# Temperature_sensing_and_heater_power.net
KiCad netlist of a schematic drawn in Altium Designer
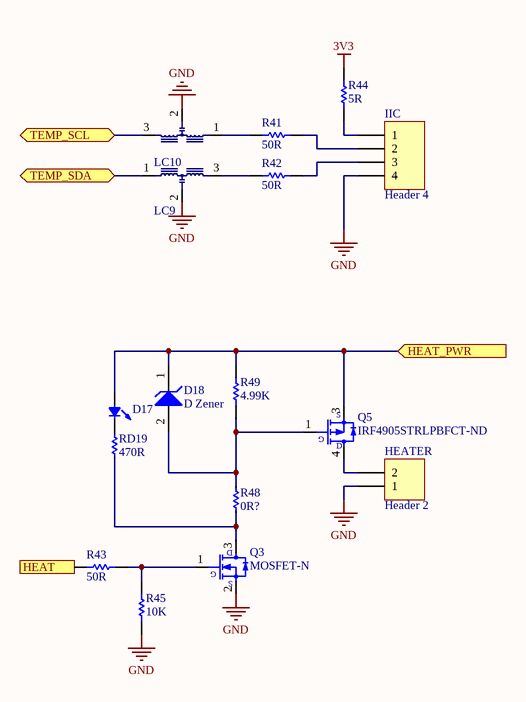
[diagram p0: Temperature sensing and heater power.SchDoc]

(export (version "E")
  (design (tool "Eeschema 10.0.6"))
  (components
    (comp (ref "D17")
      (value "LED0")
      (footprint "0603 SMT LED")
      (description "T 1 3/4 LED")
      (fields (field (name "PUBLISHER") "Altium Limited"))
      (libsource (lib "Miscellaneous Devices") (part "LED0"))
    )
    (comp (ref "D18")
      (value "D Zener")
      (footprint "SOD123/X.85")
      (description "Zener Diode")
      (fields (field (name "PUBLISHER") "Altium Limited"))
      (libsource (lib "Miscellaneous Devices") (part "D Zener"))
    )
    (comp (ref "HEATER")
      (value "Header 2")
      (footprint "Molex Mini-Fit Jr 5569 - 2 Pin, RA")
      (description "Header, 2-Pin")
      (fields (field (name "PUBLISHER") "Altium Limited"))
      (libsource (lib "Miscellaneous Connectors") (part "Header 2"))
    )
    (comp (ref "IIC")
      (value "Header 4")
      (footprint "AMPModu MTE 4 Pin Right Angle PCB-Locking Connector")
      (description "Header, 4-Pin")
      (fields (field (name "PUBLISHER") "Altium Limited"))
      (libsource (lib "Miscellaneous Connectors") (part "Header 4"))
    )
    (comp (ref "LC9")
      (value "MEM2012F")
      (footprint "MEM2012S LC Filter")
      (description "Signal Line 3-terminal Filters")
      (libsource (lib "Unsorted") (part "MEM2012F - Signal Filter"))
    )
    (comp (ref "LC10")
      (value "MEM2012F")
      (footprint "MEM2012S LC Filter")
      (description "Signal Line 3-terminal Filters")
      (libsource (lib "Unsorted") (part "MEM2012F - Signal Filter"))
    )
    (comp (ref "Q3")
      (value "MOSFET-N")
      (footprint "SOT23-3N")
      (description "N-Channel MOSFET")
      (fields (field (name "PUBLISHER") "Altium Limited"))
      (libsource (lib "Miscellaneous Devices") (part "MOSFET-N"))
    )
    (comp (ref "Q5")
      (value "IRF4905STRLPBFCT-ND")
      (footprint "TO254P1520-3_4N")
      (description "P-Channel MOSFET")
      (fields (field (name "PUBLISHER") "Altium Limited"))
      (libsource (lib "Miscellaneous Devices") (part "MOSFET-P"))
    )
    (comp (ref "R41")
      (value "50R")
      (footprint "0603R")
      (description "Semiconductor Resistor")
      (fields (field (name "Comment") "Res Semi") (field (name "PUBLISHER") "Altium Limited"))
      (libsource (lib "Miscellaneous Devices") (part "Res Semi"))
    )
    (comp (ref "R42")
      (value "50R")
      (footprint "0603R")
      (description "Semiconductor Resistor")
      (fields (field (name "Comment") "Res Semi") (field (name "PUBLISHER") "Altium Limited"))
      (libsource (lib "Miscellaneous Devices") (part "Res Semi"))
    )
    (comp (ref "R43")
      (value "50R")
      (footprint "0603R")
      (description "Semiconductor Resistor")
      (fields (field (name "Comment") "Res Semi") (field (name "PUBLISHER") "Altium Limited"))
      (libsource (lib "Miscellaneous Devices") (part "Res Semi"))
    )
    (comp (ref "R44")
      (value "5R")
      (footprint "1206R")
      (description "Semiconductor Resistor")
      (fields (field (name "Comment") "Res Semi") (field (name "PUBLISHER") "Altium Limited"))
      (libsource (lib "Miscellaneous Devices") (part "Res Semi"))
    )
    (comp (ref "R45")
      (value "10K")
      (footprint "0603R")
      (description "Semiconductor Resistor")
      (fields (field (name "Comment") "Res Semi") (field (name "PUBLISHER") "Altium Limited"))
      (libsource (lib "Miscellaneous Devices") (part "Res Semi"))
    )
    (comp (ref "R48")
      (value "0R?")
      (footprint "0603R")
      (description "Semiconductor Resistor")
      (fields (field (name "Comment") "Res Semi Small") (field (name "PUBLISHER") "Altium Limited"))
      (libsource (lib "Miscellaneous Devices") (part "Res Semi Small"))
    )
    (comp (ref "R49")
      (value "4.99K")
      (footprint "1206R")
      (description "Semiconductor Resistor")
      (fields (field (name "Comment") "Res Semi") (field (name "PUBLISHER") "Altium Limited"))
      (libsource (lib "Miscellaneous Devices") (part "Res Semi"))
    )
    (comp (ref "RD19")
      (value "470R")
      (footprint "0603R")
      (description "Semiconductor Resistor")
      (fields (field (name "Comment") "Res Semi Small") (field (name "PUBLISHER") "Altium Limited"))
      (libsource (lib "Miscellaneous Devices") (part "Res Semi Small"))
    )
  )
  (nets
    (net (code "1") (name "/HEAT") (class "Default")
      (node (ref "R43") (pin "1") (pinfunction "1_1") (pintype "passive"))
    )
    (net (code "2") (name "/HEAT_PWR") (class "Default")
      (node (ref "D17") (pin "1") (pinfunction "1_1") (pintype "passive"))
      (node (ref "D18") (pin "1") (pinfunction "A_1") (pintype "passive"))
      (node (ref "Q5") (pin "3") (pinfunction "D_3") (pintype "passive"))
      (node (ref "R49") (pin "2") (pinfunction "2_2") (pintype "passive"))
    )
    (net (code "3") (name "/TEMP_SCL") (class "Default")
      (node (ref "LC10") (pin "3") (pinfunction "3_3") (pintype "passive"))
    )
    (net (code "4") (name "/TEMP_SDA") (class "Default")
      (node (ref "LC9") (pin "1") (pinfunction "1_1") (pintype "passive"))
    )
    (net (code "5") (name "3V3") (class "Default")
      (node (ref "R44") (pin "2") (pinfunction "2_2") (pintype "passive"))
    )
    (net (code "6") (name "GND") (class "Default")
      (node (ref "HEATER") (pin "1") (pinfunction "1_1") (pintype "passive"))
      (node (ref "IIC") (pin "4") (pinfunction "4_4") (pintype "passive"))
      (node (ref "LC10") (pin "2") (pinfunction "2_2") (pintype "passive"))
      (node (ref "LC9") (pin "2") (pinfunction "2_2") (pintype "passive"))
      (node (ref "Q3") (pin "2") (pinfunction "S_2") (pintype "passive"))
      (node (ref "R45") (pin "1") (pinfunction "1_1") (pintype "passive"))
    )
    (net (code "7") (name "Net-(D17-Pad2)") (class "Default")
      (node (ref "D17") (pin "2") (pinfunction "2_2") (pintype "passive"))
      (node (ref "RD19") (pin "1") (pinfunction "1_1") (pintype "passive"))
    )
    (net (code "8") (name "Net-(D18-K)") (class "Default")
      (node (ref "D18") (pin "2") (pinfunction "K_2") (pintype "passive"))
      (node (ref "Q5") (pin "1") (pinfunction "G_1") (pintype "passive"))
      (node (ref "R48") (pin "1") (pinfunction "1_1") (pintype "passive"))
      (node (ref "R49") (pin "1") (pinfunction "1_1") (pintype "passive"))
    )
    (net (code "9") (name "Net-(IIC-Pad1)") (class "Default")
      (node (ref "IIC") (pin "1") (pinfunction "1_1") (pintype "passive"))
      (node (ref "R44") (pin "1") (pinfunction "1_1") (pintype "passive"))
    )
    (net (code "10") (name "Net-(IIC-Pad2)") (class "Default")
      (node (ref "IIC") (pin "2") (pinfunction "2_2") (pintype "passive"))
      (node (ref "R41") (pin "2") (pinfunction "2_2") (pintype "passive"))
    )
    (net (code "11") (name "Net-(IIC-Pad3)") (class "Default")
      (node (ref "IIC") (pin "3") (pinfunction "3_3") (pintype "passive"))
      (node (ref "R42") (pin "2") (pinfunction "2_2") (pintype "passive"))
    )
    (net (code "12") (name "Net-(LC9-Pad3)") (class "Default")
      (node (ref "LC9") (pin "3") (pinfunction "3_3") (pintype "passive"))
      (node (ref "R42") (pin "1") (pinfunction "1_1") (pintype "passive"))
    )
    (net (code "13") (name "Net-(LC10-Pad1)") (class "Default")
      (node (ref "LC10") (pin "1") (pinfunction "1_1") (pintype "passive"))
      (node (ref "R41") (pin "1") (pinfunction "1_1") (pintype "passive"))
    )
    (net (code "14") (name "Net-(Q3-D)") (class "Default")
      (node (ref "Q3") (pin "3") (pinfunction "D_3") (pintype "passive"))
      (node (ref "R48") (pin "2") (pinfunction "2_2") (pintype "passive"))
      (node (ref "RD19") (pin "2") (pinfunction "2_2") (pintype "passive"))
    )
    (net (code "15") (name "Net-(Q3-G)") (class "Default")
      (node (ref "Q3") (pin "1") (pinfunction "G_1") (pintype "passive"))
      (node (ref "R43") (pin "2") (pinfunction "2_2") (pintype "passive"))
      (node (ref "R45") (pin "2") (pinfunction "2_2") (pintype "passive"))
    )
    (net (code "16") (name "Net-(Q5-S)") (class "Default")
      (node (ref "HEATER") (pin "2") (pinfunction "2_2") (pintype "passive"))
      (node (ref "Q5") (pin "4") (pinfunction "S_4") (pintype "passive"))
    )
  )
)
